# main.net
KiCad netlist of a schematic drawn in EAGLE
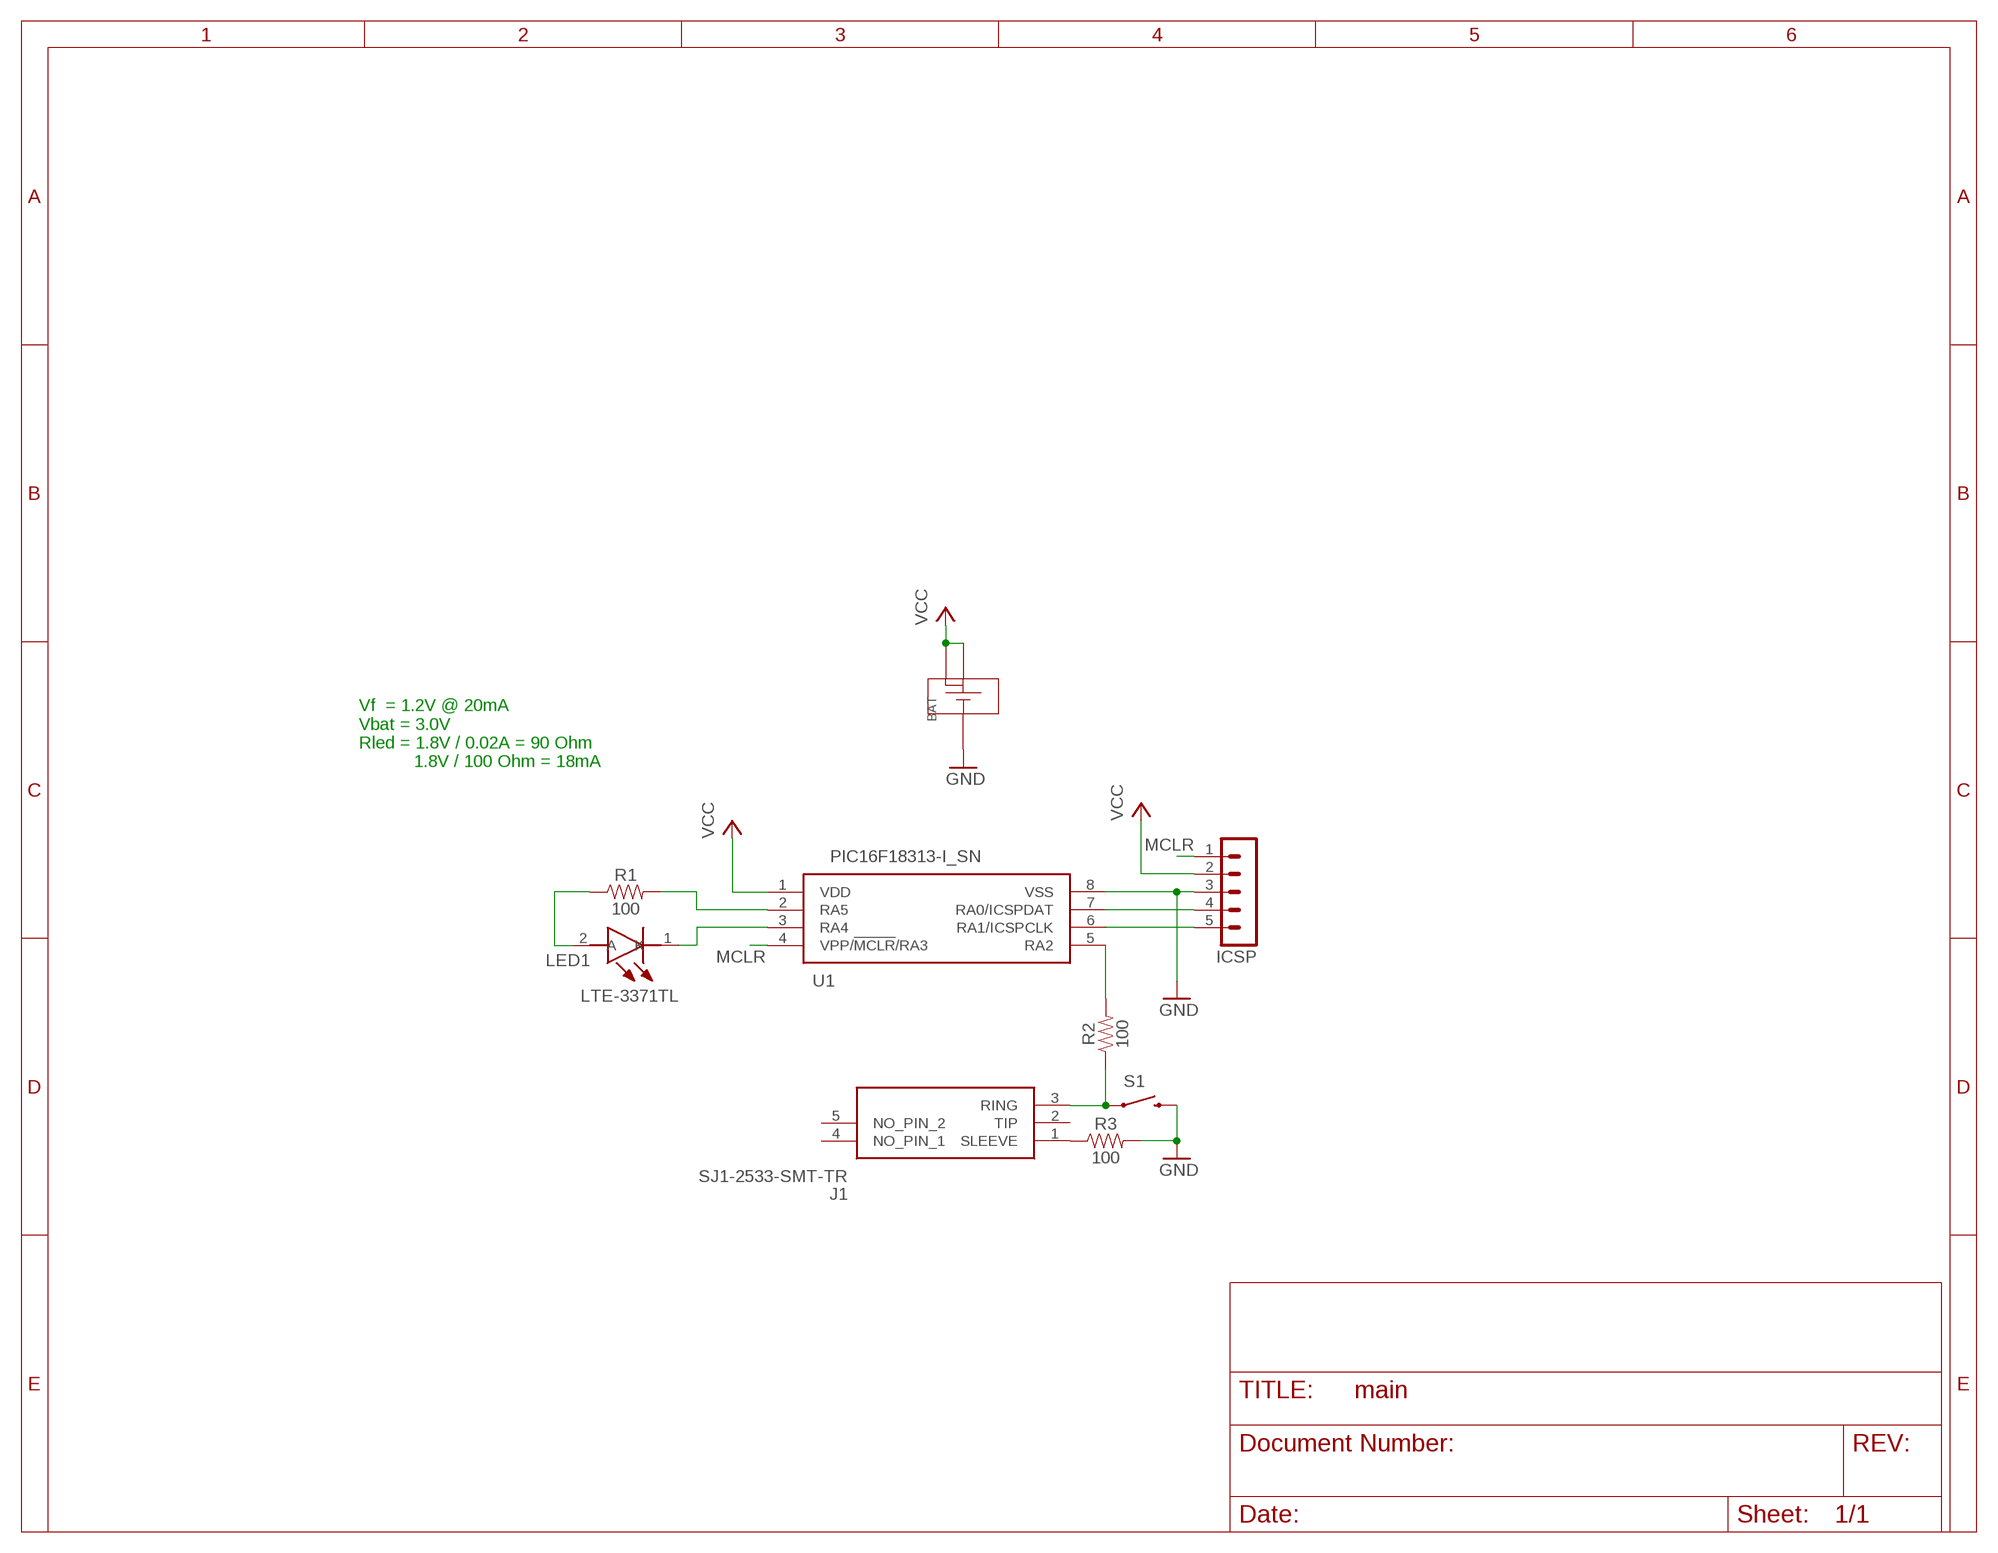
[diagram p0: schematic, sheet 1]

(export (version "E")
  (design (tool "Eeschema 10.0.6"))
  (components
    (comp (ref "BAT")
      (value "SMTM1632")
      (footprint "eagle-import:SMTM1632")
      (libsource (lib "eagle-import") (part "SMTM1632"))
    )
    (comp (ref "ICSP")
      (value "MA05-1")
      (footprint "eagle-import:MA05-1")
      (libsource (lib "eagle-import") (part "MA05-1"))
    )
    (comp (ref "J1")
      (value "SJ1-2533-SMT-TR")
      (footprint "eagle-import:SJ12533SMTTR")
      (fields (field (name "MOUSER_PART_NUMBER") "490-SJ1-2533-SMT-TR"))
      (libsource (lib "eagle-import") (part "SJ1-2533-SMT-TR"))
    )
    (comp (ref "LED1")
      (value "LTE-3371TL")
      (footprint "eagle-import:LTE3371TL")
      (fields (field (name "MOUSER_PART_NUMBER") "859-LTE-3371TL"))
      (libsource (lib "eagle-import") (part "LTE-3371TL"))
    )
    (comp (ref "R1")
      (value "100")
      (footprint "eagle-import:0603")
      (libsource (lib "eagle-import") (part "100OHM-0603-1/10W-1%"))
    )
    (comp (ref "R2")
      (value "100")
      (footprint "eagle-import:0603")
      (libsource (lib "eagle-import") (part "100OHM-0603-1/10W-1%"))
    )
    (comp (ref "R3")
      (value "100")
      (footprint "eagle-import:0603")
      (libsource (lib "eagle-import") (part "100OHM-0603-1/10W-1%"))
    )
    (comp (ref "S1")
      (value "SWITCH-MOMENTARY-2PTH")
      (footprint "eagle-import:TACTILE-PTH")
      (libsource (lib "eagle-import") (part "SWITCH-MOMENTARY-2PTH"))
    )
    (comp (ref "U1")
      (value "PIC16F18313-I_SN")
      (footprint "eagle-import:SOIC127P600X175-8N")
      (fields
        (field (name "MANUFACTURER_PART_NUMBER") "PIC16F18313-I/SN")
        (field (name "MOUSER_PART_NUMBER") "579-PIC16F18313-I/SN")
      )
      (libsource (lib "eagle-import") (part "PIC16F18313-I_SN"))
    )
  )
  (nets
    (net (code "1") (name "/MCLR") (class "Default")
      (node (ref "ICSP") (pin "1") (pinfunction "1_1") (pintype "passive"))
      (node (ref "U1") (pin "4") (pinfunction "VPP/~{MCLR}/RA3_4") (pintype "bidirectional"))
    )
    (net (code "2") (name "GND") (class "Default")
      (node (ref "BAT") (pin "1") (pinfunction "-_1") (pintype "passive"))
      (node (ref "ICSP") (pin "3") (pinfunction "3_3") (pintype "passive"))
      (node (ref "R3") (pin "2") (pinfunction "2_2") (pintype "passive"))
      (node (ref "S1") (pin "3") (pinfunction "2_3") (pintype "passive"))
      (node (ref "U1") (pin "8") (pinfunction "VSS_8") (pintype "bidirectional"))
    )
    (net (code "3") (name "Net-(J1-RING)") (class "Default")
      (node (ref "J1") (pin "3") (pinfunction "RING_3") (pintype "bidirectional"))
      (node (ref "R2") (pin "1") (pinfunction "1_1") (pintype "passive"))
      (node (ref "S1") (pin "1") (pinfunction "1_1") (pintype "passive"))
    )
    (net (code "4") (name "Net-(J1-SLEEVE)") (class "Default")
      (node (ref "J1") (pin "1") (pinfunction "SLEEVE_1") (pintype "bidirectional"))
      (node (ref "R3") (pin "1") (pinfunction "1_1") (pintype "passive"))
    )
    (net (code "5") (name "Net-(LED1-A)") (class "Default")
      (node (ref "LED1") (pin "2") (pinfunction "A_2") (pintype "bidirectional"))
      (node (ref "R1") (pin "1") (pinfunction "1_1") (pintype "passive"))
    )
    (net (code "6") (name "Net-(LED1-K)") (class "Default")
      (node (ref "LED1") (pin "1") (pinfunction "K_1") (pintype "bidirectional"))
      (node (ref "U1") (pin "3") (pinfunction "RA4_3") (pintype "bidirectional"))
    )
    (net (code "7") (name "Net-(U1-RA0{slash}ICSPDAT)") (class "Default")
      (node (ref "ICSP") (pin "4") (pinfunction "4_4") (pintype "passive"))
      (node (ref "U1") (pin "7") (pinfunction "RA0/ICSPDAT_7") (pintype "bidirectional"))
    )
    (net (code "8") (name "Net-(U1-RA1{slash}ICSPCLK)") (class "Default")
      (node (ref "ICSP") (pin "5") (pinfunction "5_5") (pintype "passive"))
      (node (ref "U1") (pin "6") (pinfunction "RA1/ICSPCLK_6") (pintype "bidirectional"))
    )
    (net (code "9") (name "Net-(U1-RA2)") (class "Default")
      (node (ref "R2") (pin "2") (pinfunction "2_2") (pintype "passive"))
      (node (ref "U1") (pin "5") (pinfunction "RA2_5") (pintype "bidirectional"))
    )
    (net (code "10") (name "Net-(U1-RA5)") (class "Default")
      (node (ref "R1") (pin "2") (pinfunction "2_2") (pintype "passive"))
      (node (ref "U1") (pin "2") (pinfunction "RA5_2") (pintype "bidirectional"))
    )
    (net (code "11") (name "VCC") (class "Default")
      (node (ref "BAT") (pin "2") (pinfunction "+_2") (pintype "passive"))
      (node (ref "BAT") (pin "3") (pinfunction "+_3") (pintype "passive"))
      (node (ref "ICSP") (pin "2") (pinfunction "2_2") (pintype "passive"))
      (node (ref "U1") (pin "1") (pinfunction "VDD_1") (pintype "bidirectional"))
    )
    (net (code "12") (name "unconnected-(J1-NO_PIN_1-Pad4)") (class "Default")
      (node (ref "J1") (pin "4") (pinfunction "NO_PIN_1_4") (pintype "bidirectional"))
    )
    (net (code "13") (name "unconnected-(J1-NO_PIN_2-Pad5)") (class "Default")
      (node (ref "J1") (pin "5") (pinfunction "NO_PIN_2_5") (pintype "bidirectional"))
    )
    (net (code "14") (name "unconnected-(J1-TIP-Pad2)") (class "Default")
      (node (ref "J1") (pin "2") (pinfunction "TIP_2") (pintype "bidirectional"))
    )
  )
)
